# Basic_Interface.net
KiCad netlist of a schematic drawn in EAGLE
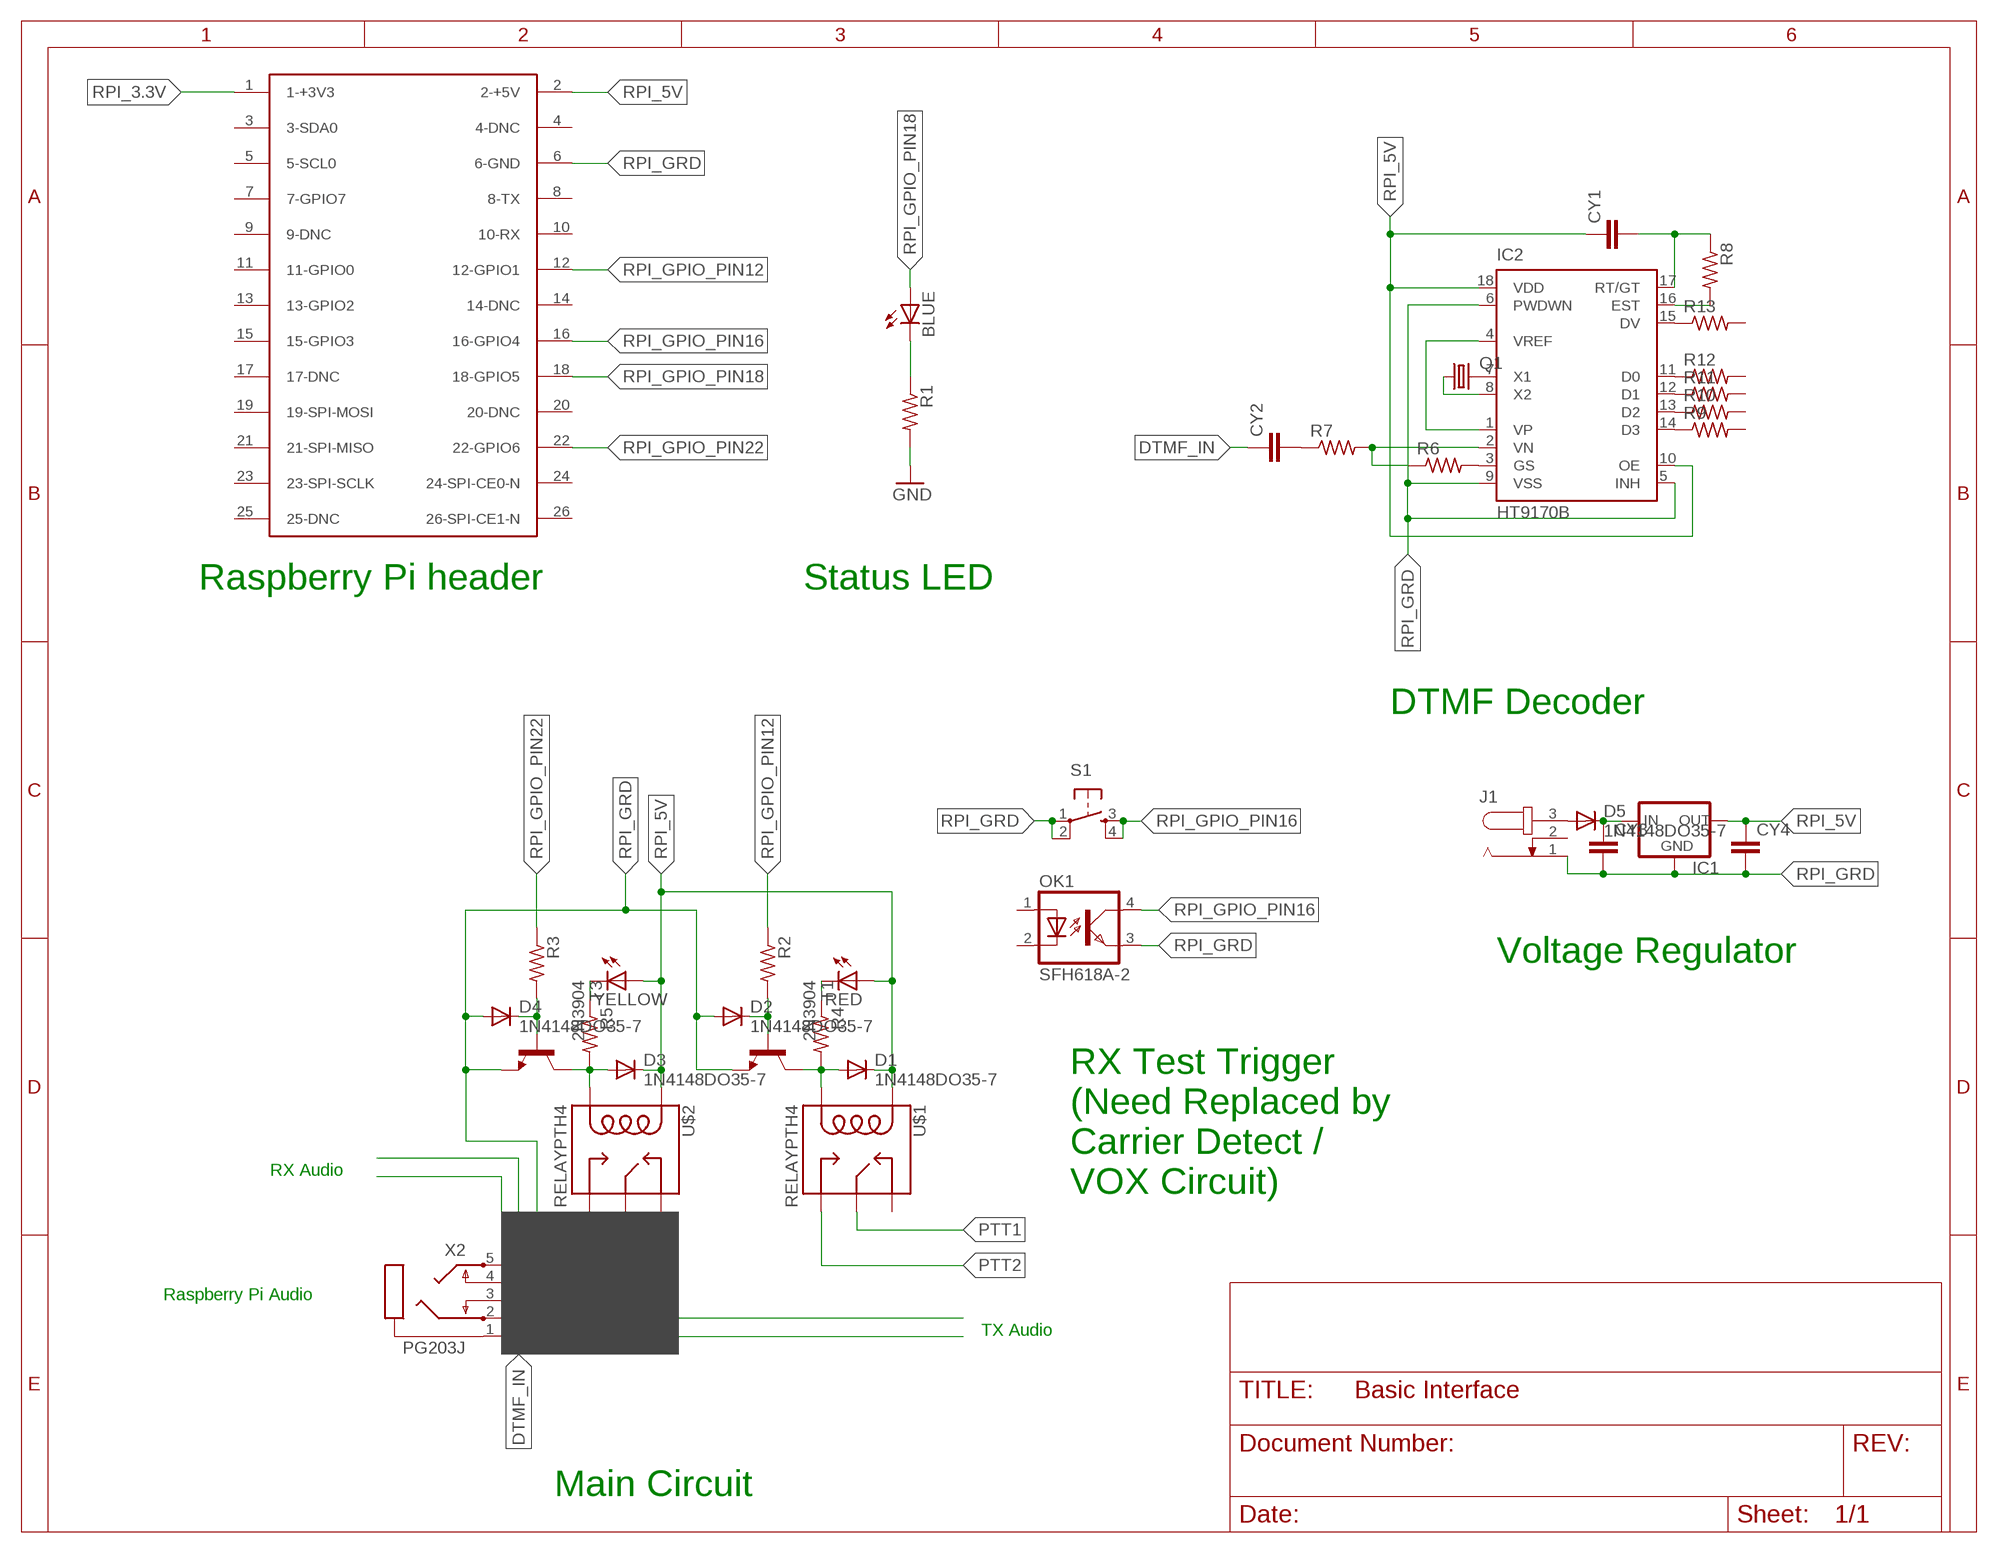
[diagram p0: schematic, sheet 1]

(export (version "E")
  (design (tool "Eeschema 10.0.6"))
  (components
    (comp (ref "BLUE")
      (value "LED3MM")
      (footprint "eagle-import:LED3MM")
      (libsource (lib "eagle-import") (part "LED3MM"))
    )
    (comp (ref "CY1")
      (value "CYYC7B5")
      (footprint "eagle-import:YC7B5")
      (libsource (lib "eagle-import") (part "CYYC7B5"))
    )
    (comp (ref "CY2")
      (value "CYYC7B5")
      (footprint "eagle-import:YC7B5")
      (libsource (lib "eagle-import") (part "CYYC7B5"))
    )
    (comp (ref "CY3")
      (value "CYYC7B5")
      (footprint "eagle-import:YC7B5")
      (libsource (lib "eagle-import") (part "CYYC7B5"))
    )
    (comp (ref "CY4")
      (value "CYYC7B5")
      (footprint "eagle-import:YC7B5")
      (libsource (lib "eagle-import") (part "CYYC7B5"))
    )
    (comp (ref "D1")
      (value "1N4148DO35-7")
      (footprint "eagle-import:DO35-7")
      (libsource (lib "eagle-import") (part "1N4148DO35-7"))
    )
    (comp (ref "D2")
      (value "1N4148DO35-7")
      (footprint "eagle-import:DO35-7")
      (libsource (lib "eagle-import") (part "1N4148DO35-7"))
    )
    (comp (ref "D3")
      (value "1N4148DO35-7")
      (footprint "eagle-import:DO35-7")
      (libsource (lib "eagle-import") (part "1N4148DO35-7"))
    )
    (comp (ref "D4")
      (value "1N4148DO35-7")
      (footprint "eagle-import:DO35-7")
      (libsource (lib "eagle-import") (part "1N4148DO35-7"))
    )
    (comp (ref "D5")
      (value "1N4148DO35-7")
      (footprint "eagle-import:DO35-7")
      (libsource (lib "eagle-import") (part "1N4148DO35-7"))
    )
    (comp (ref "IC1")
      (value "V_REG_78XX-TO-220")
      (footprint "eagle-import:TO-220-ALT")
      (libsource (lib "eagle-import") (part "V_REG_78XX-TO-220"))
    )
    (comp (ref "IC2")
      (value "HT9170B")
      (footprint "eagle-import:DIL18")
      (libsource (lib "eagle-import") (part "HT9170B"))
    )
    (comp (ref "J1")
      (value "JACK-PLUG0")
      (footprint "eagle-import:SPC4077")
      (libsource (lib "eagle-import") (part "JACK-PLUG0"))
    )
    (comp (ref "OK1")
      (value "SFH618A-2")
      (footprint "eagle-import:DIP4")
      (fields (field (name "MF") "VISHAY/TELEFUNKEN"))
      (libsource (lib "eagle-import") (part "SFH618?A-2"))
    )
    (comp (ref "Q1")
      (value "CRYSTALHC49U-V")
      (footprint "eagle-import:HC49U-V")
      (libsource (lib "eagle-import") (part "CRYSTALHC49U-V"))
    )
    (comp (ref "R1")
      (value "R-US_0204/7")
      (footprint "eagle-import:0204_7")
      (libsource (lib "eagle-import") (part "R-US_0204/7"))
    )
    (comp (ref "R2")
      (value "R-US_0204/7")
      (footprint "eagle-import:0204_7")
      (libsource (lib "eagle-import") (part "R-US_0204/7"))
    )
    (comp (ref "R3")
      (value "R-US_0204/7")
      (footprint "eagle-import:0204_7")
      (libsource (lib "eagle-import") (part "R-US_0204/7"))
    )
    (comp (ref "R4")
      (value "R-US_0204/7")
      (footprint "eagle-import:0204_7")
      (libsource (lib "eagle-import") (part "R-US_0204/7"))
    )
    (comp (ref "R5")
      (value "R-US_0204/7")
      (footprint "eagle-import:0204_7")
      (libsource (lib "eagle-import") (part "R-US_0204/7"))
    )
    (comp (ref "R6")
      (value "R-US_0204/7")
      (footprint "eagle-import:0204_7")
      (libsource (lib "eagle-import") (part "R-US_0204/7"))
    )
    (comp (ref "R7")
      (value "R-US_0204/7")
      (footprint "eagle-import:0204_7")
      (libsource (lib "eagle-import") (part "R-US_0204/7"))
    )
    (comp (ref "R8")
      (value "R-US_0204/7")
      (footprint "eagle-import:0204_7")
      (libsource (lib "eagle-import") (part "R-US_0204/7"))
    )
    (comp (ref "R9")
      (value "R-US_0204/7")
      (footprint "eagle-import:0204_7")
      (libsource (lib "eagle-import") (part "R-US_0204/7"))
    )
    (comp (ref "R10")
      (value "R-US_0204/7")
      (footprint "eagle-import:0204_7")
      (libsource (lib "eagle-import") (part "R-US_0204/7"))
    )
    (comp (ref "R11")
      (value "R-US_0204/7")
      (footprint "eagle-import:0204_7")
      (libsource (lib "eagle-import") (part "R-US_0204/7"))
    )
    (comp (ref "R12")
      (value "R-US_0204/7")
      (footprint "eagle-import:0204_7")
      (libsource (lib "eagle-import") (part "R-US_0204/7"))
    )
    (comp (ref "R13")
      (value "R-US_0204/7")
      (footprint "eagle-import:0204_7")
      (libsource (lib "eagle-import") (part "R-US_0204/7"))
    )
    (comp (ref "RED")
      (value "LED3MM")
      (footprint "eagle-import:LED3MM")
      (libsource (lib "eagle-import") (part "LED3MM"))
    )
    (comp (ref "S1")
      (value "TAC_SWITCHPTH")
      (footprint "eagle-import:TACTILE-PTH")
      (libsource (lib "eagle-import") (part "TAC_SWITCHPTH"))
    )
    (comp (ref "T1")
      (value "2N3904")
      (footprint "eagle-import:TO92")
      (libsource (lib "eagle-import") (part "2N3904"))
    )
    (comp (ref "T3")
      (value "2N3904")
      (footprint "eagle-import:TO92")
      (libsource (lib "eagle-import") (part "2N3904"))
    )
    (comp (ref "U$1")
      (value "RELAYPTH4")
      (footprint "eagle-import:RELAY-JZC")
      (libsource (lib "eagle-import") (part "RELAYPTH4"))
    )
    (comp (ref "U$2")
      (value "RELAYPTH4")
      (footprint "eagle-import:RELAY-JZC")
      (libsource (lib "eagle-import") (part "RELAYPTH4"))
    )
    (comp (ref "X1")
      (value "P1A")
      (footprint "eagle-import:RASPBERRY-PI-HEADER")
      (libsource (lib "eagle-import") (part "RASPBERRY-PIHEADER"))
    )
    (comp (ref "X2")
      (value "PG203J")
      (footprint "eagle-import:PG203J")
      (libsource (lib "eagle-import") (part "PG203J"))
    )
    (comp (ref "YELLOW")
      (value "LED3MM")
      (footprint "eagle-import:LED3MM")
      (libsource (lib "eagle-import") (part "LED3MM"))
    )
  )
  (nets
    (net (code "1") (name "DTMF_IN") (class "Default")
      (node (ref "CY2") (pin "1") (pinfunction "1_1") (pintype "passive"))
      (node (ref "U$2") (pin "4") (pinfunction "MAIN_4") (pintype "bidirectional"))
    )
    (net (code "2") (name "GND") (class "Default")
      (node (ref "R1") (pin "2") (pinfunction "2_2") (pintype "passive"))
    )
    (net (code "3") (name "Net-(BLUE-C)") (class "Default")
      (node (ref "BLUE") (pin "K") (pinfunction "C_K") (pintype "passive"))
      (node (ref "R1") (pin "1") (pinfunction "1_1") (pintype "passive"))
    )
    (net (code "4") (name "Net-(CY2-Pad2)") (class "Default")
      (node (ref "CY2") (pin "2") (pinfunction "2_2") (pintype "passive"))
      (node (ref "R7") (pin "1") (pinfunction "1_1") (pintype "passive"))
    )
    (net (code "5") (name "Net-(CY3-Pad1)") (class "Default")
      (node (ref "CY3") (pin "1") (pinfunction "1_1") (pintype "passive"))
      (node (ref "D5") (pin "C") (pinfunction "C_C") (pintype "passive"))
      (node (ref "IC1") (pin "IN") (pinfunction "IN_IN") (pintype "input"))
    )
    (net (code "6") (name "Net-(D5-PadA)") (class "Default")
      (node (ref "D5") (pin "A") (pinfunction "A_A") (pintype "passive"))
      (node (ref "J1") (pin "3") (pinfunction "3_3") (pintype "passive"))
    )
    (net (code "7") (name "Net-(IC2-D0)") (class "Default")
      (node (ref "IC2") (pin "11") (pinfunction "D0_11") (pintype "output"))
      (node (ref "R12") (pin "1") (pinfunction "1_1") (pintype "passive"))
    )
    (net (code "8") (name "Net-(IC2-D1)") (class "Default")
      (node (ref "IC2") (pin "12") (pinfunction "D1_12") (pintype "output"))
      (node (ref "R11") (pin "1") (pinfunction "1_1") (pintype "passive"))
    )
    (net (code "9") (name "Net-(IC2-D2)") (class "Default")
      (node (ref "IC2") (pin "13") (pinfunction "D2_13") (pintype "output"))
      (node (ref "R10") (pin "1") (pinfunction "1_1") (pintype "passive"))
    )
    (net (code "10") (name "Net-(IC2-D3)") (class "Default")
      (node (ref "IC2") (pin "14") (pinfunction "D3_14") (pintype "output"))
      (node (ref "R9") (pin "1") (pinfunction "1_1") (pintype "passive"))
    )
    (net (code "11") (name "Net-(IC2-DV)") (class "Default")
      (node (ref "IC2") (pin "15") (pinfunction "DV_15") (pintype "output"))
      (node (ref "R13") (pin "1") (pinfunction "1_1") (pintype "passive"))
    )
    (net (code "12") (name "Net-(IC2-EST)") (class "Default")
      (node (ref "IC2") (pin "16") (pinfunction "EST_16") (pintype "output"))
      (node (ref "R8") (pin "2") (pinfunction "2_2") (pintype "passive"))
    )
    (net (code "13") (name "Net-(IC2-GS)") (class "Default")
      (node (ref "IC2") (pin "3") (pinfunction "GS_3") (pintype "passive"))
      (node (ref "R6") (pin "2") (pinfunction "2_2") (pintype "passive"))
    )
    (net (code "14") (name "Net-(IC2-RT{slash}GT)") (class "Default")
      (node (ref "CY1") (pin "2") (pinfunction "2_2") (pintype "passive"))
      (node (ref "IC2") (pin "17") (pinfunction "RT/GT_17") (pintype "bidirectional"))
      (node (ref "R8") (pin "1") (pinfunction "1_1") (pintype "passive"))
    )
    (net (code "15") (name "Net-(IC2-VN)") (class "Default")
      (node (ref "IC2") (pin "2") (pinfunction "VN_2") (pintype "input"))
      (node (ref "R6") (pin "1") (pinfunction "1_1") (pintype "passive"))
      (node (ref "R7") (pin "2") (pinfunction "2_2") (pintype "passive"))
    )
    (net (code "16") (name "Net-(IC2-VP)") (class "Default")
      (node (ref "IC2") (pin "1") (pinfunction "VP_1") (pintype "input"))
      (node (ref "IC2") (pin "4") (pinfunction "VREF_4") (pintype "output"))
    )
    (net (code "17") (name "Net-(IC2-X1)") (class "Default")
      (node (ref "IC2") (pin "7") (pinfunction "X1_7") (pintype "input"))
      (node (ref "Q1") (pin "2") (pinfunction "2_2") (pintype "passive"))
    )
    (net (code "18") (name "Net-(IC2-X2)") (class "Default")
      (node (ref "IC2") (pin "8") (pinfunction "X2_8") (pintype "output"))
      (node (ref "Q1") (pin "1") (pinfunction "1_1") (pintype "passive"))
    )
    (net (code "19") (name "Net-(RED-C)") (class "Default")
      (node (ref "R4") (pin "1") (pinfunction "1_1") (pintype "passive"))
      (node (ref "RED") (pin "K") (pinfunction "C_K") (pintype "passive"))
    )
    (net (code "20") (name "Net-(T1-B)") (class "Default")
      (node (ref "D2") (pin "C") (pinfunction "C_C") (pintype "passive"))
      (node (ref "R2") (pin "2") (pinfunction "2_2") (pintype "passive"))
      (node (ref "T1") (pin "2") (pinfunction "B_2") (pintype "passive"))
    )
    (net (code "21") (name "Net-(T1-C)") (class "Default")
      (node (ref "D1") (pin "A") (pinfunction "A_A") (pintype "passive"))
      (node (ref "R4") (pin "2") (pinfunction "2_2") (pintype "passive"))
      (node (ref "T1") (pin "1") (pinfunction "C_1") (pintype "passive"))
      (node (ref "U$1") (pin "1") (pinfunction "COIL2_1") (pintype "bidirectional"))
    )
    (net (code "22") (name "Net-(T3-B)") (class "Default")
      (node (ref "D4") (pin "C") (pinfunction "C_C") (pintype "passive"))
      (node (ref "R3") (pin "2") (pinfunction "2_2") (pintype "passive"))
      (node (ref "T3") (pin "2") (pinfunction "B_2") (pintype "passive"))
    )
    (net (code "23") (name "Net-(T3-C)") (class "Default")
      (node (ref "D3") (pin "A") (pinfunction "A_A") (pintype "passive"))
      (node (ref "R5") (pin "2") (pinfunction "2_2") (pintype "passive"))
      (node (ref "T3") (pin "1") (pinfunction "C_1") (pintype "passive"))
      (node (ref "U$2") (pin "1") (pinfunction "COIL2_1") (pintype "bidirectional"))
    )
    (net (code "24") (name "Net-(U$2-NC)") (class "Default")
      (node (ref "U$2") (pin "2") (pinfunction "NC_2") (pintype "bidirectional"))
      (node (ref "X2") (pin "5") (pinfunction "5_5") (pintype "passive"))
    )
    (net (code "25") (name "Net-(YELLOW-C)") (class "Default")
      (node (ref "R5") (pin "1") (pinfunction "1_1") (pintype "passive"))
      (node (ref "YELLOW") (pin "K") (pinfunction "C_K") (pintype "passive"))
    )
    (net (code "26") (name "PTT1") (class "Default")
      (node (ref "U$1") (pin "4") (pinfunction "MAIN_4") (pintype "bidirectional"))
    )
    (net (code "27") (name "PTT2") (class "Default")
      (node (ref "U$1") (pin "3") (pinfunction "NO_3") (pintype "bidirectional"))
    )
    (net (code "28") (name "RPI_3.3V") (class "Default")
      (node (ref "X1") (pin "1") (pinfunction "1-+3V3_1") (pintype "bidirectional"))
    )
    (net (code "29") (name "RPI_5V") (class "Default")
      (node (ref "CY1") (pin "1") (pinfunction "1_1") (pintype "passive"))
      (node (ref "CY4") (pin "1") (pinfunction "1_1") (pintype "passive"))
      (node (ref "D1") (pin "C") (pinfunction "C_C") (pintype "passive"))
      (node (ref "D3") (pin "C") (pinfunction "C_C") (pintype "passive"))
      (node (ref "IC1") (pin "OUT") (pinfunction "OUT_OUT") (pintype "output"))
      (node (ref "IC2") (pin "10") (pinfunction "OE_10") (pintype "input"))
      (node (ref "IC2") (pin "18") (pinfunction "VDD_18") (pintype "power_in"))
      (node (ref "RED") (pin "A") (pinfunction "A_A") (pintype "passive"))
      (node (ref "U$1") (pin "5") (pinfunction "COIL1_5") (pintype "bidirectional"))
      (node (ref "U$2") (pin "5") (pinfunction "COIL1_5") (pintype "bidirectional"))
      (node (ref "X1") (pin "2") (pinfunction "2-+5V_2") (pintype "bidirectional"))
      (node (ref "YELLOW") (pin "A") (pinfunction "A_A") (pintype "passive"))
    )
    (net (code "30") (name "RPI_GPIO_PIN12") (class "Default")
      (node (ref "R2") (pin "1") (pinfunction "1_1") (pintype "passive"))
      (node (ref "X1") (pin "12") (pinfunction "12-GPIO1_12") (pintype "bidirectional"))
    )
    (net (code "31") (name "RPI_GPIO_PIN16") (class "Default")
      (node (ref "OK1") (pin "4") (pinfunction "COL_4") (pintype "passive"))
      (node (ref "S1") (pin "3") (pinfunction "3_3") (pintype "passive"))
      (node (ref "S1") (pin "4") (pinfunction "4_4") (pintype "passive"))
      (node (ref "X1") (pin "16") (pinfunction "16-GPIO4_16") (pintype "bidirectional"))
    )
    (net (code "32") (name "RPI_GPIO_PIN18") (class "Default")
      (node (ref "BLUE") (pin "A") (pinfunction "A_A") (pintype "passive"))
      (node (ref "X1") (pin "18") (pinfunction "18-GPIO5_18") (pintype "bidirectional"))
    )
    (net (code "33") (name "RPI_GPIO_PIN22") (class "Default")
      (node (ref "R3") (pin "1") (pinfunction "1_1") (pintype "passive"))
      (node (ref "X1") (pin "22") (pinfunction "22-GPIO6_22") (pintype "bidirectional"))
    )
    (net (code "34") (name "RPI_GRD") (class "Default")
      (node (ref "CY3") (pin "2") (pinfunction "2_2") (pintype "passive"))
      (node (ref "CY4") (pin "2") (pinfunction "2_2") (pintype "passive"))
      (node (ref "D2") (pin "A") (pinfunction "A_A") (pintype "passive"))
      (node (ref "D4") (pin "A") (pinfunction "A_A") (pintype "passive"))
      (node (ref "IC1") (pin "GND") (pinfunction "GND_GND") (pintype "input"))
      (node (ref "IC2") (pin "5") (pinfunction "INH_5") (pintype "input"))
      (node (ref "IC2") (pin "6") (pinfunction "PWDWN_6") (pintype "input"))
      (node (ref "IC2") (pin "9") (pinfunction "VSS_9") (pintype "power_in"))
      (node (ref "J1") (pin "1") (pinfunction "1_1") (pintype "passive"))
      (node (ref "OK1") (pin "3") (pinfunction "EMIT_3") (pintype "passive"))
      (node (ref "S1") (pin "1") (pinfunction "1_1") (pintype "passive"))
      (node (ref "S1") (pin "2") (pinfunction "2_2") (pintype "passive"))
      (node (ref "T1") (pin "3") (pinfunction "E_3") (pintype "passive"))
      (node (ref "T3") (pin "3") (pinfunction "E_3") (pintype "passive"))
      (node (ref "X1") (pin "6") (pinfunction "6-GND_6") (pintype "bidirectional"))
      (node (ref "X2") (pin "1") (pinfunction "1_1") (pintype "passive"))
    )
    (net (code "35") (name "unconnected-(J1-Pad2)") (class "Default")
      (node (ref "J1") (pin "2") (pinfunction "2_2") (pintype "passive"))
    )
    (net (code "36") (name "unconnected-(OK1-A-Pad1)") (class "Default")
      (node (ref "OK1") (pin "1") (pinfunction "A_1") (pintype "passive"))
    )
    (net (code "37") (name "unconnected-(OK1-C-Pad2)") (class "Default")
      (node (ref "OK1") (pin "2") (pinfunction "C_2") (pintype "passive"))
    )
    (net (code "38") (name "unconnected-(R9-Pad2)") (class "Default")
      (node (ref "R9") (pin "2") (pinfunction "2_2") (pintype "passive"))
    )
    (net (code "39") (name "unconnected-(R10-Pad2)") (class "Default")
      (node (ref "R10") (pin "2") (pinfunction "2_2") (pintype "passive"))
    )
    (net (code "40") (name "unconnected-(R11-Pad2)") (class "Default")
      (node (ref "R11") (pin "2") (pinfunction "2_2") (pintype "passive"))
    )
    (net (code "41") (name "unconnected-(R12-Pad2)") (class "Default")
      (node (ref "R12") (pin "2") (pinfunction "2_2") (pintype "passive"))
    )
    (net (code "42") (name "unconnected-(R13-Pad2)") (class "Default")
      (node (ref "R13") (pin "2") (pinfunction "2_2") (pintype "passive"))
    )
    (net (code "43") (name "unconnected-(U$1-NC-Pad2)") (class "Default")
      (node (ref "U$1") (pin "2") (pinfunction "NC_2") (pintype "bidirectional"))
    )
    (net (code "44") (name "unconnected-(U$2-NO-Pad3)") (class "Default")
      (node (ref "U$2") (pin "3") (pinfunction "NO_3") (pintype "bidirectional"))
    )
    (net (code "45") (name "unconnected-(X1-3-SDA0-Pad3)") (class "Default")
      (node (ref "X1") (pin "3") (pinfunction "3-SDA0_3") (pintype "bidirectional"))
    )
    (net (code "46") (name "unconnected-(X1-4-DNC-Pad4)") (class "Default")
      (node (ref "X1") (pin "4") (pinfunction "4-DNC_4") (pintype "bidirectional"))
    )
    (net (code "47") (name "unconnected-(X1-5-SCL0-Pad5)") (class "Default")
      (node (ref "X1") (pin "5") (pinfunction "5-SCL0_5") (pintype "bidirectional"))
    )
    (net (code "48") (name "unconnected-(X1-7-GPIO7-Pad7)") (class "Default")
      (node (ref "X1") (pin "7") (pinfunction "7-GPIO7_7") (pintype "bidirectional"))
    )
    (net (code "49") (name "unconnected-(X1-8-TX-Pad8)") (class "Default")
      (node (ref "X1") (pin "8") (pinfunction "8-TX_8") (pintype "bidirectional"))
    )
    (net (code "50") (name "unconnected-(X1-9-DNC-Pad9)") (class "Default")
      (node (ref "X1") (pin "9") (pinfunction "9-DNC_9") (pintype "bidirectional"))
    )
    (net (code "51") (name "unconnected-(X1-10-RX-Pad10)") (class "Default")
      (node (ref "X1") (pin "10") (pinfunction "10-RX_10") (pintype "bidirectional"))
    )
    (net (code "52") (name "unconnected-(X1-11-GPIO0-Pad11)") (class "Default")
      (node (ref "X1") (pin "11") (pinfunction "11-GPIO0_11") (pintype "bidirectional"))
    )
    (net (code "53") (name "unconnected-(X1-13-GPIO2-Pad13)") (class "Default")
      (node (ref "X1") (pin "13") (pinfunction "13-GPIO2_13") (pintype "bidirectional"))
    )
    (net (code "54") (name "unconnected-(X1-14-DNC-Pad14)") (class "Default")
      (node (ref "X1") (pin "14") (pinfunction "14-DNC_14") (pintype "bidirectional"))
    )
    (net (code "55") (name "unconnected-(X1-15-GPIO3-Pad15)") (class "Default")
      (node (ref "X1") (pin "15") (pinfunction "15-GPIO3_15") (pintype "bidirectional"))
    )
    (net (code "56") (name "unconnected-(X1-17-DNC-Pad17)") (class "Default")
      (node (ref "X1") (pin "17") (pinfunction "17-DNC_17") (pintype "bidirectional"))
    )
    (net (code "57") (name "unconnected-(X1-19-SPI-MOSI-Pad19)") (class "Default")
      (node (ref "X1") (pin "19") (pinfunction "19-SPI-MOSI_19") (pintype "bidirectional"))
    )
    (net (code "58") (name "unconnected-(X1-20-DNC-Pad20)") (class "Default")
      (node (ref "X1") (pin "20") (pinfunction "20-DNC_20") (pintype "bidirectional"))
    )
    (net (code "59") (name "unconnected-(X1-21-SPI-MISO-Pad21)") (class "Default")
      (node (ref "X1") (pin "21") (pinfunction "21-SPI-MISO_21") (pintype "bidirectional"))
    )
    (net (code "60") (name "unconnected-(X1-23-SPI-SCLK-Pad23)") (class "Default")
      (node (ref "X1") (pin "23") (pinfunction "23-SPI-SCLK_23") (pintype "bidirectional"))
    )
    (net (code "61") (name "unconnected-(X1-24-SPI-CE0-N-Pad24)") (class "Default")
      (node (ref "X1") (pin "24") (pinfunction "24-SPI-CE0-N_24") (pintype "bidirectional"))
    )
    (net (code "62") (name "unconnected-(X1-25-DNC-Pad25)") (class "Default")
      (node (ref "X1") (pin "25") (pinfunction "25-DNC_25") (pintype "bidirectional"))
    )
    (net (code "63") (name "unconnected-(X1-26-SPI-CE1-N-Pad26)") (class "Default")
      (node (ref "X1") (pin "26") (pinfunction "26-SPI-CE1-N_26") (pintype "bidirectional"))
    )
    (net (code "64") (name "unconnected-(X2-Pad2)") (class "Default")
      (node (ref "X2") (pin "2") (pinfunction "2_2") (pintype "passive"))
    )
    (net (code "65") (name "unconnected-(X2-Pad3)") (class "Default")
      (node (ref "X2") (pin "3") (pinfunction "3_3") (pintype "passive"))
    )
    (net (code "66") (name "unconnected-(X2-Pad4)") (class "Default")
      (node (ref "X2") (pin "4") (pinfunction "4_4") (pintype "passive"))
    )
  )
)
